# SCH_VoltageRegulator_2021-10-16.net
KiCad netlist of a schematic drawn in EasyEDA
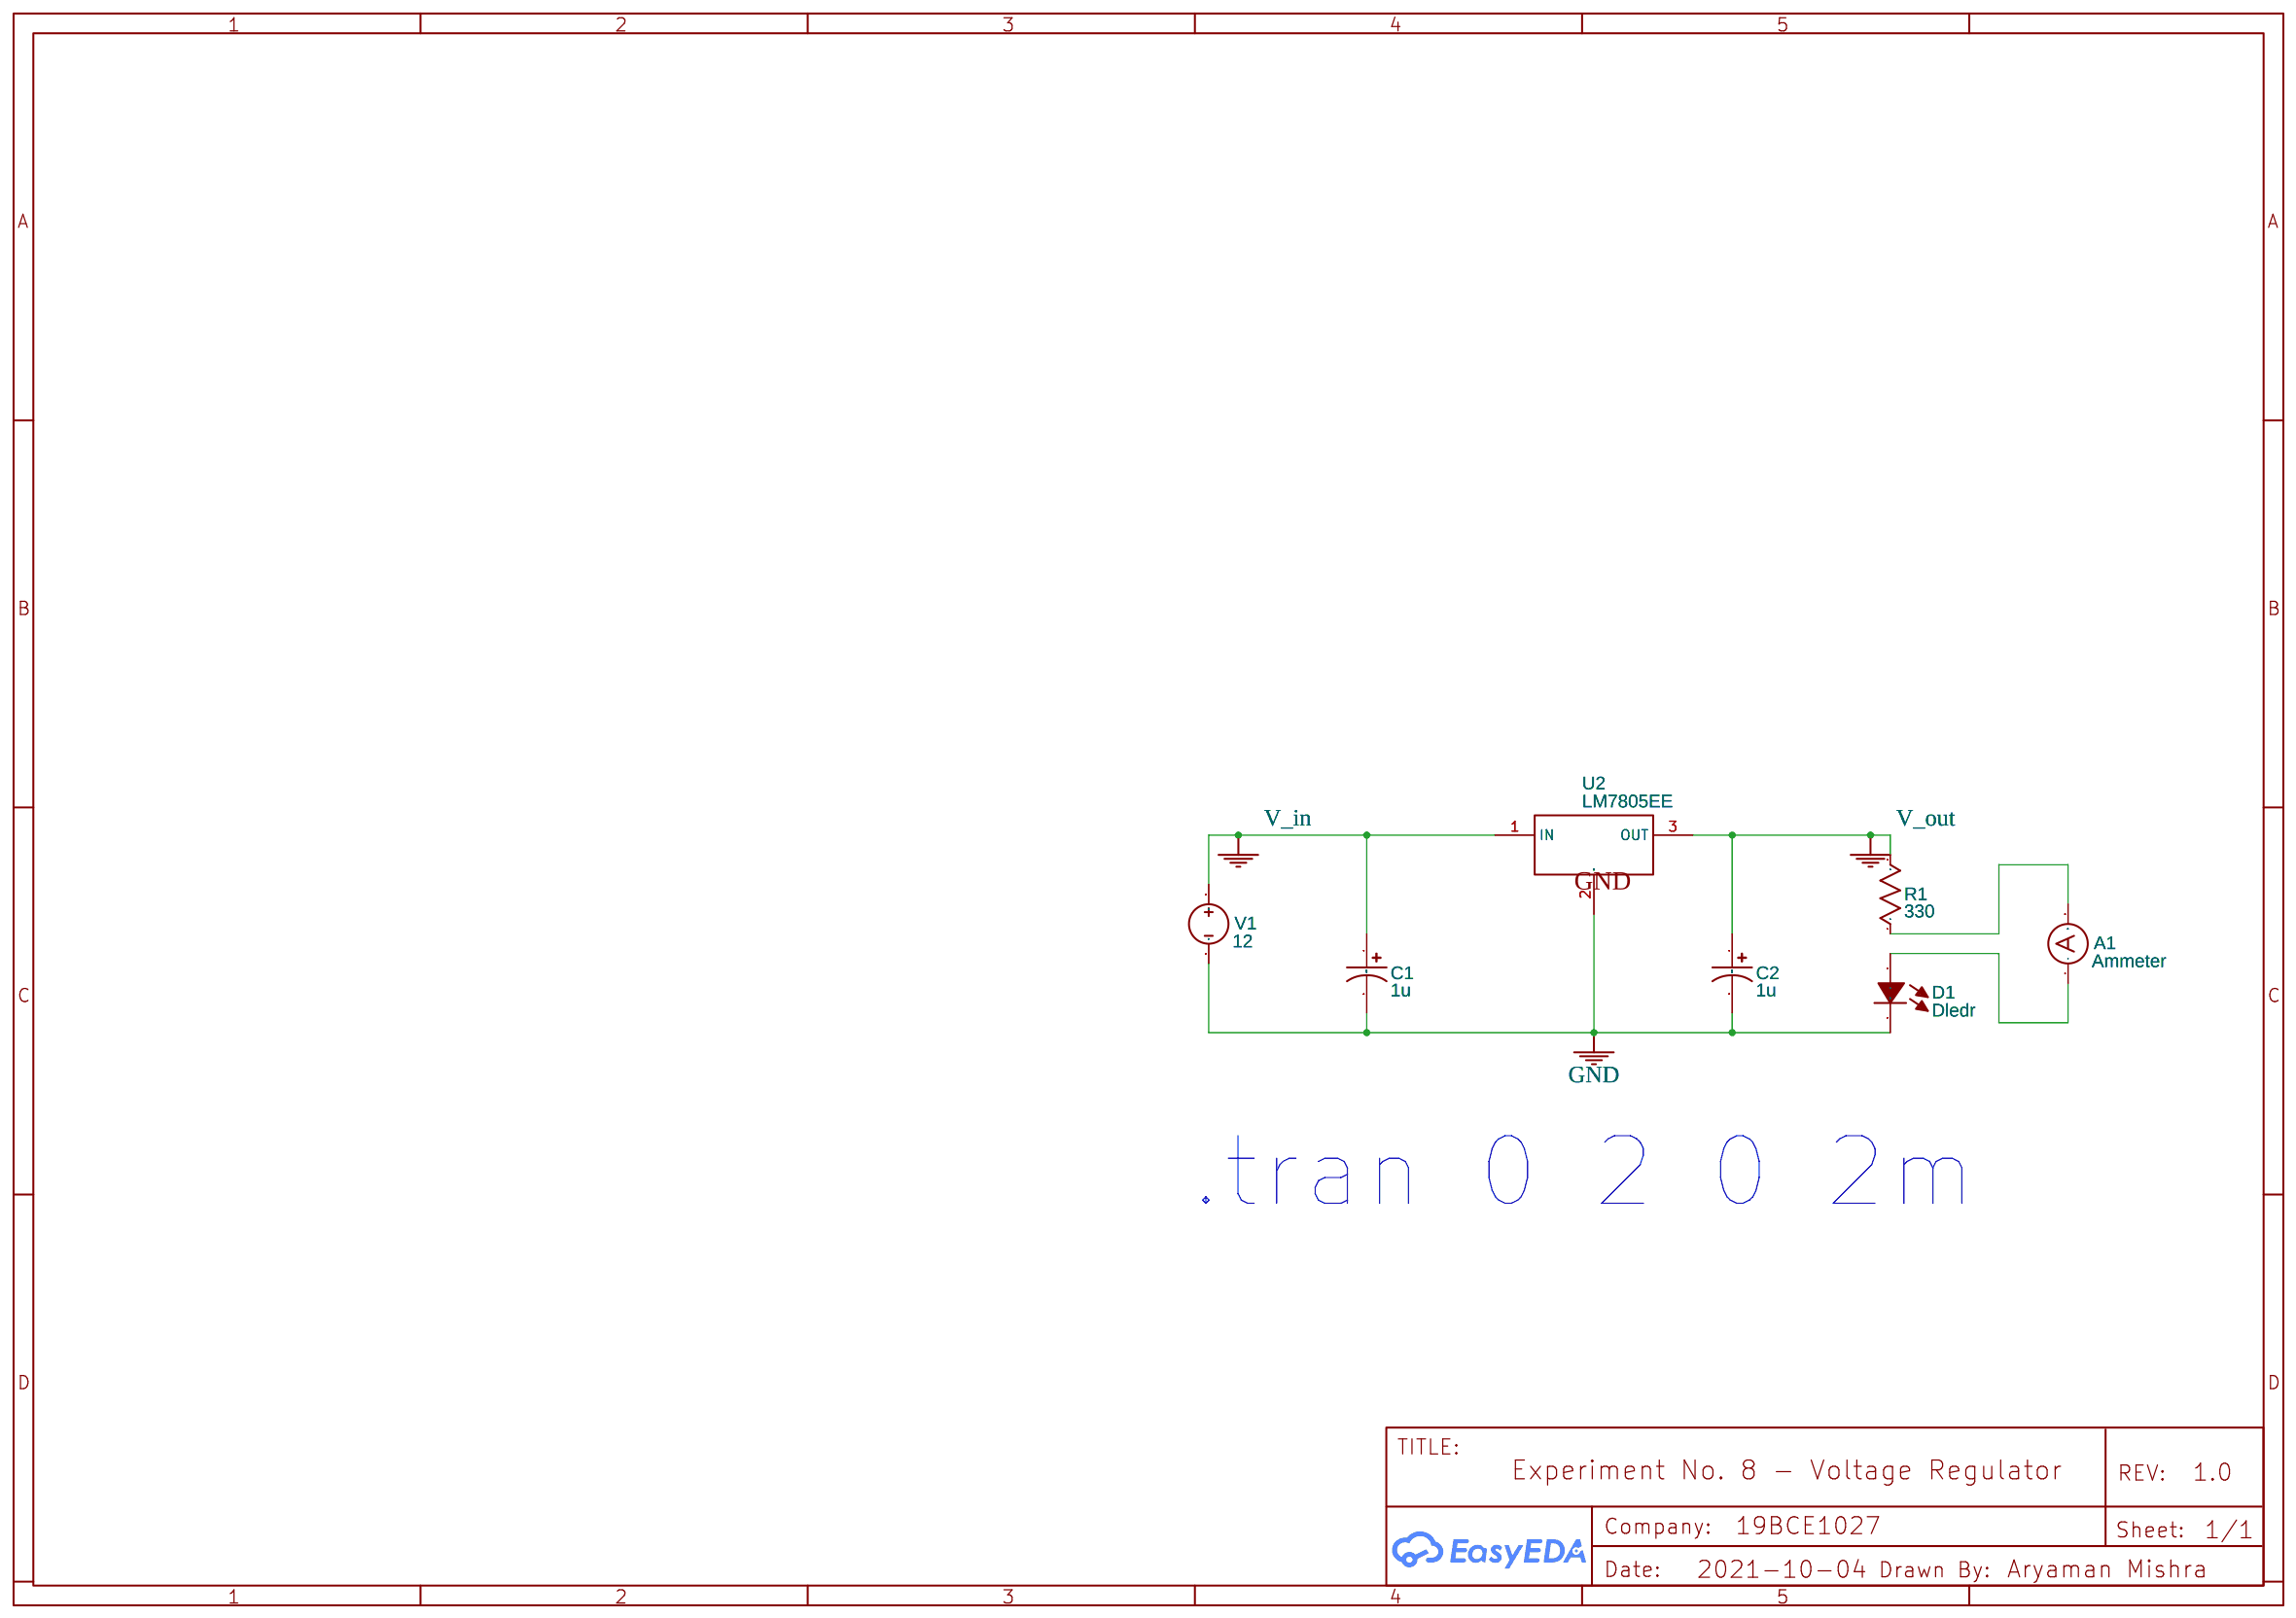
[diagram p0: schematic sheet]

(export (version "E")
  (design (tool "Eeschema 10.0.6"))
  (components
    (comp (ref "A1") (value "Ammeter") (libsource (lib "") (part "AMMETER")))
    (comp (ref "C1") (value "1u") (libsource (lib "") (part "CE_SMD_D4.0×H5.5_US")))
    (comp (ref "C2") (value "1u") (libsource (lib "") (part "CE_SMD_D4.0×H5.5_US")))
    (comp (ref "D1") (value "Dledr") (libsource (lib "") (part "DLEDR")))
    (comp (ref "R1") (value "330") (libsource (lib "") (part "R_0603_US")))
    (comp (ref "U2") (value "LM7805EE") (libsource (lib "") (part "78XX")))
    (comp (ref "V1") (value "12") (libsource (lib "") (part "VDC")))
  )
  (nets
    (net (code "1") (name "GND") (class "Default")
      (node (ref "C1") (pin "2") (pinfunction "2_2") (pintype "unspecified"))
      (node (ref "C2") (pin "2") (pinfunction "2_2") (pintype "unspecified"))
      (node (ref "D1") (pin "2") (pinfunction "C_2") (pintype "unspecified"))
      (node (ref "U2") (pin "2") (pinfunction "GND_2") (pintype "passive"))
      (node (ref "V1") (pin "2") (pinfunction "2_2") (pintype "unspecified"))
    )
    (net (code "2") (name "Net-(A1-+)") (class "Default")
      (node (ref "A1") (pin "1") (pinfunction "+_1") (pintype "unspecified"))
      (node (ref "D1") (pin "1") (pinfunction "A_1") (pintype "unspecified"))
    )
    (net (code "3") (name "Net-(A1-Pad2)") (class "Default")
      (node (ref "A1") (pin "2") (pinfunction "2_2") (pintype "unspecified"))
      (node (ref "R1") (pin "1") (pinfunction "1_1") (pintype "unspecified"))
    )
    (net (code "4") (name "V_in") (class "Default")
      (node (ref "C1") (pin "1") (pinfunction "1_1") (pintype "unspecified"))
      (node (ref "U2") (pin "1") (pinfunction "IN_1") (pintype "passive"))
      (node (ref "V1") (pin "1") (pinfunction "1_1") (pintype "unspecified"))
    )
    (net (code "5") (name "V_out") (class "Default")
      (node (ref "C2") (pin "1") (pinfunction "1_1") (pintype "unspecified"))
      (node (ref "R1") (pin "2") (pinfunction "2_2") (pintype "unspecified"))
      (node (ref "U2") (pin "3") (pinfunction "OUT_3") (pintype "passive"))
    )
  )
)
